# esp32_moisture.net
KiCad netlist of a schematic drawn in EAGLE
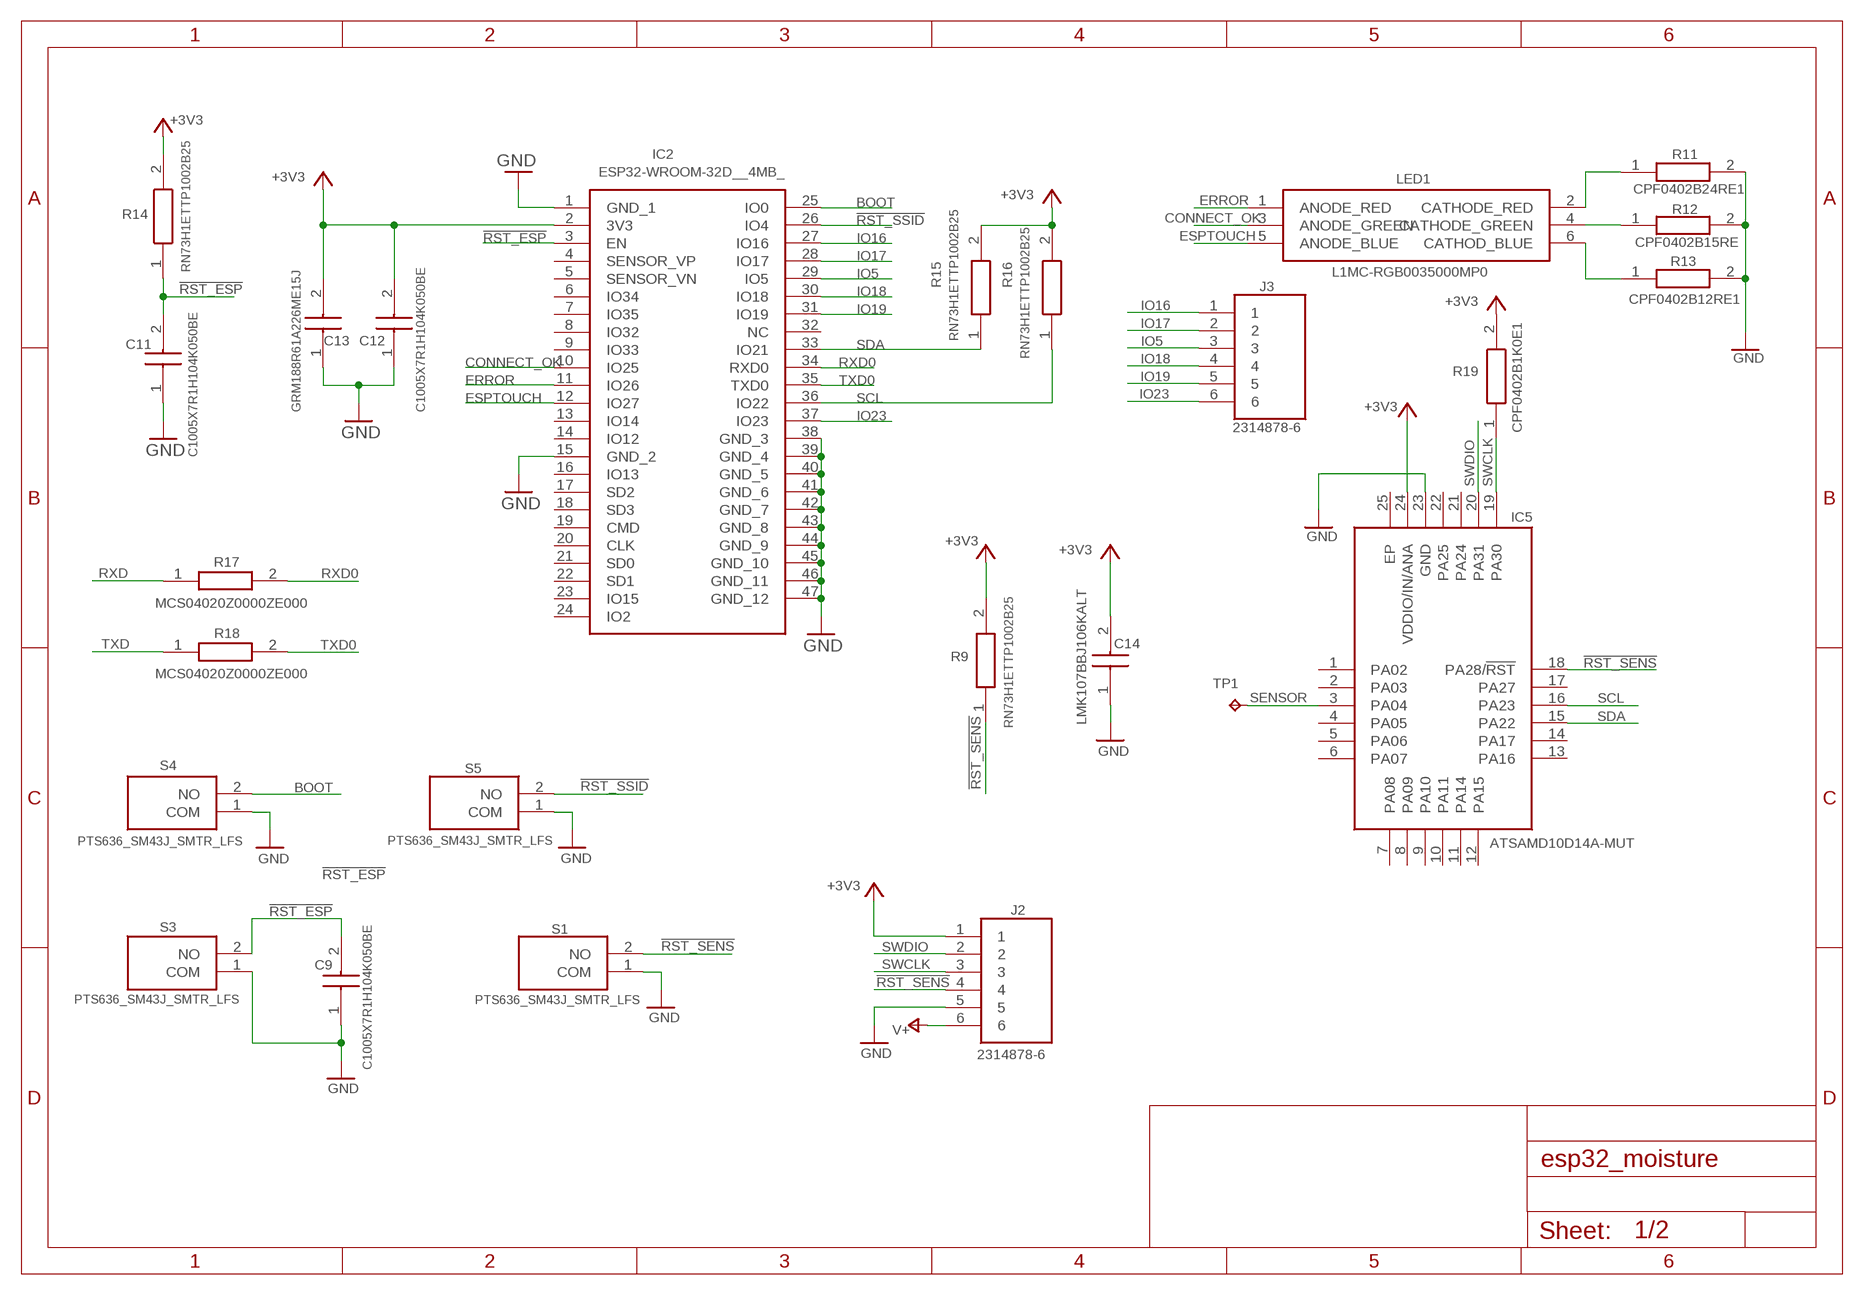
[diagram p0: schematic, sheet 1]
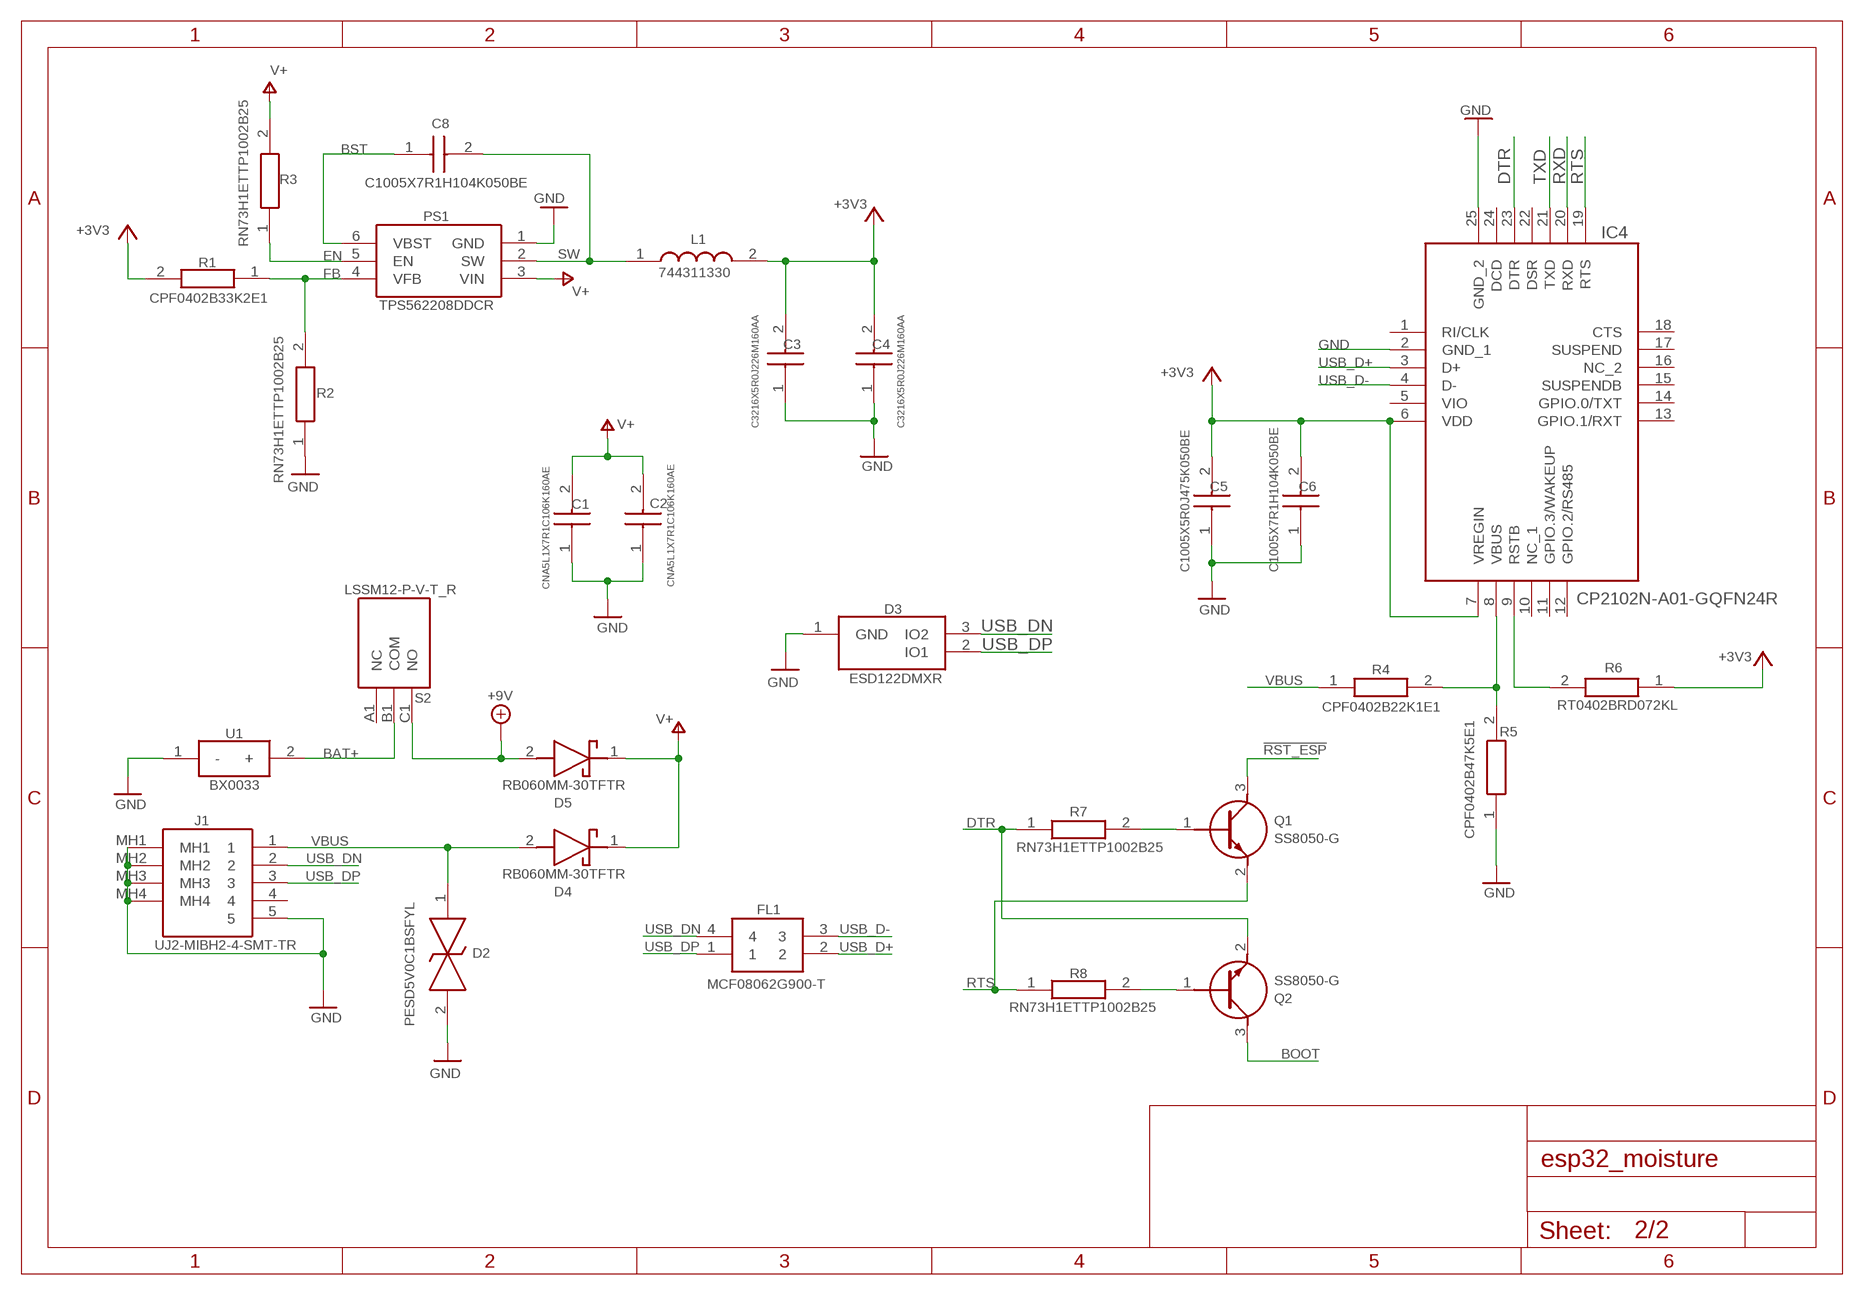
[diagram p1: schematic, sheet 2]

(export (version "E")
  (design (tool "Eeschema 10.0.6"))
  (components
    (comp (ref "C9")
      (value "C1005X7R1H104K050BE")
      (footprint "eagle-import:CAPC1005X55N")
      (fields (field (name "MOUSER2_PART_NUMBER") "810-C1005X7R1H104KBE"))
      (libsource (lib "eagle-import") (part "C1005X7R1H104K050BE"))
    )
    (comp (ref "C11")
      (value "C1005X7R1H104K050BE")
      (footprint "eagle-import:CAPC1005X55N")
      (fields (field (name "MOUSER2_PART_NUMBER") "810-C1005X7R1H104KBE"))
      (libsource (lib "eagle-import") (part "C1005X7R1H104K050BE"))
    )
    (comp (ref "C12")
      (value "C1005X7R1H104K050BE")
      (footprint "eagle-import:CAPC1005X55N")
      (fields (field (name "MOUSER2_PART_NUMBER") "810-C1005X7R1H104KBE"))
      (libsource (lib "eagle-import") (part "C1005X7R1H104K050BE"))
    )
    (comp (ref "C13")
      (value "GRM188R61A226ME15J")
      (footprint "eagle-import:CAPC1608X90N")
      (fields (field (name "MOUSER2_PART_NUMBER") "81-GRM188R61A226ME5J"))
      (libsource (lib "eagle-import") (part "GRM188R61A226ME15J"))
    )
    (comp (ref "C14")
      (value "LMK107BBJ106KALT")
      (footprint "eagle-import:CAPC1608X100N")
      (fields (field (name "MOUSER2_PART_NUMBER") "963-LMK107BBJ106KALT"))
      (libsource (lib "eagle-import") (part "LMK107BBJ106KALT"))
    )
    (comp (ref "IC2")
      (value "ESP32-WROOM-32D__4MB_")
      (footprint "eagle-import:ESP32WROOM32D4MB")
      (fields
        (field (name "MANUFACTURER_PART_NUMBER") "ESP32-WROOM-32D (4MB)")
        (field (name "MOUSER_PART_NUMBER") "356-ESP32WROOM-32D")
      )
      (libsource (lib "eagle-import") (part "ESP32-WROOM-32D__4MB_"))
    )
    (comp (ref "IC5")
      (value "ATSAMD10D14A-MUT")
      (footprint "eagle-import:QFN50P400X400X90-25N")
      (fields (field (name "MOUSER_PART_NUMBER") "556-ATSAMD10D14A-MUT"))
      (libsource (lib "eagle-import") (part "ATSAMD10D14A-MUT"))
    )
    (comp (ref "J2")
      (value "2314878-6")
      (footprint "eagle-import:RHDR6W40P0X200_1X6_1200X210X45")
      (libsource (lib "eagle-import") (part "2314878-6"))
    )
    (comp (ref "J3")
      (value "2314878-6")
      (footprint "eagle-import:RHDR6W40P0X200_1X6_1200X210X45")
      (libsource (lib "eagle-import") (part "2314878-6"))
    )
    (comp (ref "LED1")
      (value "L1MC-RGB0035000MP0")
      (footprint "eagle-import:L1MCRGB0035000MP0")
      (libsource (lib "eagle-import") (part "L1MC-RGB0035000MP0"))
    )
    (comp (ref "R9")
      (value "RN73H1ETTP1002B25")
      (footprint "eagle-import:RESC1005X40N")
      (fields (field (name "MOUSER2_PART_NUMBER") "660-RN73H1ETP1002B25"))
      (libsource (lib "eagle-import") (part "RN73H1ETTP1002B25"))
    )
    (comp (ref "R11")
      (value "CPF0402B24RE1")
      (footprint "eagle-import:RESC1005X35N")
      (libsource (lib "eagle-import") (part "CPF0402B24RE1"))
    )
    (comp (ref "R12")
      (value "CPF0402B15RE")
      (footprint "eagle-import:RESC1005X35N")
      (libsource (lib "eagle-import") (part "CPF0402B15RE"))
    )
    (comp (ref "R13")
      (value "CPF0402B12RE1")
      (footprint "eagle-import:RESC1005X35N")
      (libsource (lib "eagle-import") (part "CPF0402B12RE1"))
    )
    (comp (ref "R14")
      (value "RN73H1ETTP1002B25")
      (footprint "eagle-import:RESC1005X40N")
      (fields (field (name "MOUSER2_PART_NUMBER") "660-RN73H1ETP1002B25"))
      (libsource (lib "eagle-import") (part "RN73H1ETTP1002B25"))
    )
    (comp (ref "R15")
      (value "RN73H1ETTP1002B25")
      (footprint "eagle-import:RESC1005X40N")
      (fields (field (name "MOUSER2_PART_NUMBER") "660-RN73H1ETP1002B25"))
      (libsource (lib "eagle-import") (part "RN73H1ETTP1002B25"))
    )
    (comp (ref "R16")
      (value "RN73H1ETTP1002B25")
      (footprint "eagle-import:RESC1005X40N")
      (fields (field (name "MOUSER2_PART_NUMBER") "660-RN73H1ETP1002B25"))
      (libsource (lib "eagle-import") (part "RN73H1ETTP1002B25"))
    )
    (comp (ref "R17")
      (value "MCS04020Z0000ZE000")
      (footprint "eagle-import:RESC1005X37N")
      (libsource (lib "eagle-import") (part "MCS04020Z0000ZE000"))
    )
    (comp (ref "R18")
      (value "MCS04020Z0000ZE000")
      (footprint "eagle-import:RESC1005X37N")
      (libsource (lib "eagle-import") (part "MCS04020Z0000ZE000"))
    )
    (comp (ref "R19")
      (value "CPF0402B1K0E1")
      (footprint "eagle-import:RESC1005X35N")
      (fields (field (name "MOUSER2_PART_NUMBER") "279-CPF0402B1K0E1"))
      (libsource (lib "eagle-import") (part "CPF0402B1K0E1"))
    )
    (comp (ref "S1")
      (value "PTS636_SM43J_SMTR_LFS")
      (footprint "eagle-import:PTS636SM43JSMTRLFS")
      (fields (field (name "MANUFACTURER_PART_NUMBER") "PTS636 SM43J SMTR LFS"))
      (libsource (lib "eagle-import") (part "PTS636_SM43J_SMTR_LFS"))
    )
    (comp (ref "S3")
      (value "PTS636_SM43J_SMTR_LFS")
      (footprint "eagle-import:PTS636SM43JSMTRLFS")
      (fields (field (name "MANUFACTURER_PART_NUMBER") "PTS636 SM43J SMTR LFS"))
      (libsource (lib "eagle-import") (part "PTS636_SM43J_SMTR_LFS"))
    )
    (comp (ref "S4")
      (value "PTS636_SM43J_SMTR_LFS")
      (footprint "eagle-import:PTS636SM43JSMTRLFS")
      (fields (field (name "MANUFACTURER_PART_NUMBER") "PTS636 SM43J SMTR LFS"))
      (libsource (lib "eagle-import") (part "PTS636_SM43J_SMTR_LFS"))
    )
    (comp (ref "S5")
      (value "PTS636_SM43J_SMTR_LFS")
      (footprint "eagle-import:PTS636SM43JSMTRLFS")
      (fields (field (name "MANUFACTURER_PART_NUMBER") "PTS636 SM43J SMTR LFS"))
      (libsource (lib "eagle-import") (part "PTS636_SM43J_SMTR_LFS"))
    )
    (comp (ref "TP1")
      (value "TPTP15R")
      (footprint "eagle-import:TP15R")
      (libsource (lib "eagle-import") (part "TPTP15R"))
    )
    (comp (ref "C1")
      (value "CNA5L1X7R1C106K160AE")
      (footprint "eagle-import:CAPC3216X180N")
      (fields (field (name "MOUSER2_PART_NUMBER") "810-CNA5L1X7R1C106K1"))
      (libsource (lib "eagle-import") (part "CNA5L1X7R1C106K160AE"))
    )
    (comp (ref "C2")
      (value "CNA5L1X7R1C106K160AE")
      (footprint "eagle-import:CAPC3216X180N")
      (fields (field (name "MOUSER2_PART_NUMBER") "810-CNA5L1X7R1C106K1"))
      (libsource (lib "eagle-import") (part "CNA5L1X7R1C106K160AE"))
    )
    (comp (ref "C3")
      (value "C3216X5R0J226M160AA")
      (footprint "eagle-import:CAPC3216X180N")
      (libsource (lib "eagle-import") (part "C3216X5R0J226M160AA"))
    )
    (comp (ref "C4")
      (value "C3216X5R0J226M160AA")
      (footprint "eagle-import:CAPC3216X180N")
      (libsource (lib "eagle-import") (part "C3216X5R0J226M160AA"))
    )
    (comp (ref "C5")
      (value "C1005X5R0J475K050BE")
      (footprint "eagle-import:CAPC1005X55N")
      (libsource (lib "eagle-import") (part "C1005X5R0J475K050BE"))
    )
    (comp (ref "C6")
      (value "C1005X7R1H104K050BE")
      (footprint "eagle-import:CAPC1005X55N")
      (fields (field (name "MOUSER2_PART_NUMBER") "810-C1005X7R1H104KBE"))
      (libsource (lib "eagle-import") (part "C1005X7R1H104K050BE"))
    )
    (comp (ref "C8")
      (value "C1005X7R1H104K050BE")
      (footprint "eagle-import:CAPC1005X55N")
      (fields (field (name "MOUSER2_PART_NUMBER") "810-C1005X7R1H104KBE"))
      (libsource (lib "eagle-import") (part "C1005X7R1H104K050BE"))
    )
    (comp (ref "D2")
      (value "PESD5V0C1BSFYL")
      (footprint "eagle-import:PESD5V0S1USF315")
      (fields (field (name "MOUSER2_PART_NUMBER") "771-PESD5V0C1BSFYL"))
      (libsource (lib "eagle-import") (part "PESD5V0C1BSFYL"))
    )
    (comp (ref "D3")
      (value "ESD122DMXR")
      (footprint "eagle-import:DMX0003A")
      (libsource (lib "eagle-import") (part "ESD122DMXR"))
    )
    (comp (ref "D4")
      (value "RB060MM-30TFTR")
      (footprint "eagle-import:SODFL3516X90N")
      (fields (field (name "MOUSER2_PART_NUMBER") "755-RB060MM-30TFTR"))
      (libsource (lib "eagle-import") (part "RB060MM-30TFTR"))
    )
    (comp (ref "D5")
      (value "RB060MM-30TFTR")
      (footprint "eagle-import:SODFL3516X90N")
      (fields (field (name "MOUSER2_PART_NUMBER") "755-RB060MM-30TFTR"))
      (libsource (lib "eagle-import") (part "RB060MM-30TFTR"))
    )
    (comp (ref "FL1")
      (value "MCF08062G900-T")
      (footprint "eagle-import:MCF08062G900T")
      (fields (field (name "MOUSER_PART_NUMBER") "963-MCF08062G900-T"))
      (libsource (lib "eagle-import") (part "MCF08062G900-T"))
    )
    (comp (ref "IC4")
      (value "CP2102N-A01-GQFN24R")
      (footprint "eagle-import:QFN50P400X400X80-25N")
      (fields (field (name "MOUSER2_PART_NUMBER") "634-CP02NA01GQFN24R"))
      (libsource (lib "eagle-import") (part "CP2102N-A01-GQFN24R"))
    )
    (comp (ref "J1")
      (value "UJ2-MIBH2-4-SMT-TR")
      (footprint "eagle-import:UJ2MIBH24SMTTR")
      (fields (field (name "MOUSER2_PART_NUMBER") "490-UJ2-MIBH2-4-SMT"))
      (libsource (lib "eagle-import") (part "UJ2-MIBH2-4-SMT-TR"))
    )
    (comp (ref "L1")
      (value "744311330")
      (footprint "eagle-import:WE-HCI_7030_7040_705023")
      (libsource (lib "eagle-import") (part "744311330"))
    )
    (comp (ref "PS1")
      (value "TPS562208DDCR")
      (footprint "eagle-import:SOT95P280X110-6N")
      (fields (field (name "MOUSER_PART_NUMBER") "595-TPS562208DDCR"))
      (libsource (lib "eagle-import") (part "TPS562208DDCR"))
    )
    (comp (ref "Q1")
      (value "SS8050-G")
      (footprint "eagle-import:SOT95P240X115-3N")
      (fields (field (name "MOUSER2_PART_NUMBER") "750-SS8050-G"))
      (libsource (lib "eagle-import") (part "SS8050-G"))
    )
    (comp (ref "Q2")
      (value "SS8050-G")
      (footprint "eagle-import:SOT95P240X115-3N")
      (fields (field (name "MOUSER2_PART_NUMBER") "750-SS8050-G"))
      (libsource (lib "eagle-import") (part "SS8050-G"))
    )
    (comp (ref "R1")
      (value "CPF0402B33K2E1")
      (footprint "eagle-import:RESC1005X35N")
      (libsource (lib "eagle-import") (part "CPF0402B33K2E1"))
    )
    (comp (ref "R2")
      (value "RN73H1ETTP1002B25")
      (footprint "eagle-import:RESC1005X40N")
      (fields (field (name "MOUSER2_PART_NUMBER") "660-RN73H1ETP1002B25"))
      (libsource (lib "eagle-import") (part "RN73H1ETTP1002B25"))
    )
    (comp (ref "R3")
      (value "RN73H1ETTP1002B25")
      (footprint "eagle-import:RESC1005X40N")
      (fields (field (name "MOUSER2_PART_NUMBER") "660-RN73H1ETP1002B25"))
      (libsource (lib "eagle-import") (part "RN73H1ETTP1002B25"))
    )
    (comp (ref "R4")
      (value "CPF0402B22K1E1")
      (footprint "eagle-import:RESC1005X35N")
      (libsource (lib "eagle-import") (part "CPF0402B22K1E1"))
    )
    (comp (ref "R5")
      (value "CPF0402B47K5E1")
      (footprint "eagle-import:RESC1005X35N")
      (libsource (lib "eagle-import") (part "CPF0402B47K5E1"))
    )
    (comp (ref "R6")
      (value "RT0402BRD072KL")
      (footprint "eagle-import:RESC1005X35N")
      (libsource (lib "eagle-import") (part "RT0402BRD072KL"))
    )
    (comp (ref "R7")
      (value "RN73H1ETTP1002B25")
      (footprint "eagle-import:RESC1005X40N")
      (fields (field (name "MOUSER2_PART_NUMBER") "660-RN73H1ETP1002B25"))
      (libsource (lib "eagle-import") (part "RN73H1ETTP1002B25"))
    )
    (comp (ref "R8")
      (value "RN73H1ETTP1002B25")
      (footprint "eagle-import:RESC1005X40N")
      (fields (field (name "MOUSER2_PART_NUMBER") "660-RN73H1ETP1002B25"))
      (libsource (lib "eagle-import") (part "RN73H1ETTP1002B25"))
    )
    (comp (ref "S2")
      (value "LSSM12-P-V-T_R")
      (footprint "eagle-import:LSSM12PVTR")
      (fields
        (field (name "MANUFACTURER_PART_NUMBER") "LSSM12-P-V-T/R")
        (field (name "MOUSER_PART_NUMBER") "113-LSSM12PVT/R")
      )
      (libsource (lib "eagle-import") (part "LSSM12-P-V-T_R"))
    )
    (comp (ref "U1")
      (value "BX0033")
      (footprint "eagle-import:BX0033")
      (fields (field (name "MOUSER_PART_NUMBER") "122-BX0033"))
      (libsource (lib "eagle-import") (part "BX0033"))
    )
  )
  (nets
    (net (code "1") (name "+3V3") (class "Default")
      (node (ref "C12") (pin "2") (pinfunction "2_2") (pintype "bidirectional"))
      (node (ref "C13") (pin "2") (pinfunction "2_2") (pintype "bidirectional"))
      (node (ref "C14") (pin "2") (pinfunction "2_2") (pintype "bidirectional"))
      (node (ref "C3") (pin "2") (pinfunction "2_2") (pintype "bidirectional"))
      (node (ref "C4") (pin "2") (pinfunction "2_2") (pintype "bidirectional"))
      (node (ref "C5") (pin "2") (pinfunction "2_2") (pintype "bidirectional"))
      (node (ref "C6") (pin "2") (pinfunction "2_2") (pintype "bidirectional"))
      (node (ref "IC2") (pin "2") (pinfunction "3V3_2") (pintype "bidirectional"))
      (node (ref "IC4") (pin "6") (pinfunction "VDD_6") (pintype "bidirectional"))
      (node (ref "IC4") (pin "7") (pinfunction "VREGIN_7") (pintype "bidirectional"))
      (node (ref "IC5") (pin "24") (pinfunction "VDDIO/IN/ANA_24") (pintype "bidirectional"))
      (node (ref "J2") (pin "1") (pinfunction "1_1") (pintype "bidirectional"))
      (node (ref "L1") (pin "2") (pinfunction "2_2") (pintype "bidirectional"))
      (node (ref "R1") (pin "2") (pinfunction "2_2") (pintype "bidirectional"))
      (node (ref "R14") (pin "2") (pinfunction "2_2") (pintype "bidirectional"))
      (node (ref "R15") (pin "2") (pinfunction "2_2") (pintype "bidirectional"))
      (node (ref "R16") (pin "2") (pinfunction "2_2") (pintype "bidirectional"))
      (node (ref "R19") (pin "2") (pinfunction "2_2") (pintype "bidirectional"))
      (node (ref "R6") (pin "1") (pinfunction "1_1") (pintype "bidirectional"))
      (node (ref "R9") (pin "2") (pinfunction "2_2") (pintype "bidirectional"))
    )
    (net (code "2") (name "+9V") (class "Default")
      (node (ref "D5") (pin "2") (pinfunction "A_2") (pintype "bidirectional"))
      (node (ref "S2") (pin "C1") (pinfunction "NO_C1") (pintype "bidirectional"))
    )
    (net (code "3") (name "BAT+") (class "Default")
      (node (ref "S2") (pin "B1") (pinfunction "COM_B1") (pintype "bidirectional"))
      (node (ref "U1") (pin "2") (pinfunction "+_2") (pintype "bidirectional"))
    )
    (net (code "4") (name "BOOT") (class "Default")
      (node (ref "IC2") (pin "25") (pinfunction "IO0_25") (pintype "bidirectional"))
      (node (ref "Q2") (pin "3") (pinfunction "C_3") (pintype "bidirectional"))
      (node (ref "S4") (pin "2") (pinfunction "NO_2") (pintype "bidirectional"))
    )
    (net (code "5") (name "BST") (class "Default")
      (node (ref "C8") (pin "1") (pinfunction "1_1") (pintype "bidirectional"))
      (node (ref "PS1") (pin "6") (pinfunction "VBST_6") (pintype "bidirectional"))
    )
    (net (code "6") (name "CONNECT_OK") (class "Default")
      (node (ref "IC2") (pin "10") (pinfunction "IO25_10") (pintype "bidirectional"))
      (node (ref "LED1") (pin "3") (pinfunction "ANODE_GREEN_3") (pintype "bidirectional"))
    )
    (net (code "7") (name "DTR") (class "Default")
      (node (ref "IC4") (pin "23") (pinfunction "DTR_23") (pintype "bidirectional"))
      (node (ref "Q2") (pin "2") (pinfunction "E_2") (pintype "bidirectional"))
      (node (ref "R7") (pin "1") (pinfunction "1_1") (pintype "bidirectional"))
    )
    (net (code "8") (name "EN") (class "Default")
      (node (ref "PS1") (pin "5") (pinfunction "EN_5") (pintype "bidirectional"))
      (node (ref "R3") (pin "1") (pinfunction "1_1") (pintype "bidirectional"))
    )
    (net (code "9") (name "ERROR") (class "Default")
      (node (ref "IC2") (pin "11") (pinfunction "IO26_11") (pintype "bidirectional"))
      (node (ref "LED1") (pin "1") (pinfunction "ANODE_RED_1") (pintype "bidirectional"))
    )
    (net (code "10") (name "ESPTOUCH") (class "Default")
      (node (ref "IC2") (pin "12") (pinfunction "IO27_12") (pintype "bidirectional"))
      (node (ref "LED1") (pin "5") (pinfunction "ANODE_BLUE_5") (pintype "bidirectional"))
    )
    (net (code "11") (name "FB") (class "Default")
      (node (ref "PS1") (pin "4") (pinfunction "VFB_4") (pintype "bidirectional"))
      (node (ref "R1") (pin "1") (pinfunction "1_1") (pintype "bidirectional"))
      (node (ref "R2") (pin "2") (pinfunction "2_2") (pintype "bidirectional"))
    )
    (net (code "12") (name "GND") (class "Default")
      (node (ref "C1") (pin "1") (pinfunction "1_1") (pintype "bidirectional"))
      (node (ref "C11") (pin "1") (pinfunction "1_1") (pintype "bidirectional"))
      (node (ref "C12") (pin "1") (pinfunction "1_1") (pintype "bidirectional"))
      (node (ref "C13") (pin "1") (pinfunction "1_1") (pintype "bidirectional"))
      (node (ref "C14") (pin "1") (pinfunction "1_1") (pintype "bidirectional"))
      (node (ref "C2") (pin "1") (pinfunction "1_1") (pintype "bidirectional"))
      (node (ref "C3") (pin "1") (pinfunction "1_1") (pintype "bidirectional"))
      (node (ref "C4") (pin "1") (pinfunction "1_1") (pintype "bidirectional"))
      (node (ref "C5") (pin "1") (pinfunction "1_1") (pintype "bidirectional"))
      (node (ref "C6") (pin "1") (pinfunction "1_1") (pintype "bidirectional"))
      (node (ref "C9") (pin "1") (pinfunction "1_1") (pintype "bidirectional"))
      (node (ref "D2") (pin "2") (pinfunction "2_2") (pintype "bidirectional"))
      (node (ref "D3") (pin "1") (pinfunction "GND_1") (pintype "bidirectional"))
      (node (ref "IC2") (pin "1") (pinfunction "GND_1_1") (pintype "bidirectional"))
      (node (ref "IC2") (pin "15") (pinfunction "GND_2_15") (pintype "bidirectional"))
      (node (ref "IC2") (pin "38") (pinfunction "GND_3_38") (pintype "bidirectional"))
      (node (ref "IC2") (pin "39") (pinfunction "GND_4_39") (pintype "bidirectional"))
      (node (ref "IC2") (pin "40") (pinfunction "GND_5_40") (pintype "bidirectional"))
      (node (ref "IC2") (pin "41") (pinfunction "GND_6_41") (pintype "bidirectional"))
      (node (ref "IC2") (pin "42") (pinfunction "GND_7_42") (pintype "bidirectional"))
      (node (ref "IC2") (pin "43") (pinfunction "GND_8_43") (pintype "bidirectional"))
      (node (ref "IC2") (pin "44") (pinfunction "GND_9_44") (pintype "bidirectional"))
      (node (ref "IC2") (pin "45") (pinfunction "GND_10_45") (pintype "bidirectional"))
      (node (ref "IC2") (pin "46") (pinfunction "GND_11_46") (pintype "bidirectional"))
      (node (ref "IC2") (pin "47") (pinfunction "GND_12_47") (pintype "bidirectional"))
      (node (ref "IC4") (pin "2") (pinfunction "GND_1_2") (pintype "bidirectional"))
      (node (ref "IC4") (pin "25") (pinfunction "GND_2_25") (pintype "bidirectional"))
      (node (ref "IC5") (pin "23") (pinfunction "GND_23") (pintype "bidirectional"))
      (node (ref "J1") (pin "5") (pinfunction "5_5") (pintype "bidirectional"))
      (node (ref "J1") (pin "MH1") (pinfunction "MH1_MH1") (pintype "bidirectional"))
      (node (ref "J1") (pin "MH2") (pinfunction "MH2_MH2") (pintype "bidirectional"))
      (node (ref "J1") (pin "MH3") (pinfunction "MH3_MH3") (pintype "bidirectional"))
      (node (ref "J1") (pin "MH4") (pinfunction "MH4_MH4") (pintype "bidirectional"))
      (node (ref "J2") (pin "5") (pinfunction "5_5") (pintype "bidirectional"))
      (node (ref "PS1") (pin "1") (pinfunction "GND_1") (pintype "bidirectional"))
      (node (ref "R11") (pin "2") (pinfunction "2_2") (pintype "bidirectional"))
      (node (ref "R12") (pin "2") (pinfunction "2_2") (pintype "bidirectional"))
      (node (ref "R13") (pin "2") (pinfunction "2_2") (pintype "bidirectional"))
      (node (ref "R2") (pin "1") (pinfunction "1_1") (pintype "bidirectional"))
      (node (ref "R5") (pin "1") (pinfunction "1_1") (pintype "bidirectional"))
      (node (ref "S1") (pin "1") (pinfunction "COM_1") (pintype "bidirectional"))
      (node (ref "S3") (pin "1") (pinfunction "COM_1") (pintype "bidirectional"))
      (node (ref "S4") (pin "1") (pinfunction "COM_1") (pintype "bidirectional"))
      (node (ref "S5") (pin "1") (pinfunction "COM_1") (pintype "bidirectional"))
      (node (ref "U1") (pin "1") (pinfunction "-_1") (pintype "bidirectional"))
    )
    (net (code "13") (name "IO5") (class "Default")
      (node (ref "IC2") (pin "29") (pinfunction "IO5_29") (pintype "bidirectional"))
      (node (ref "J3") (pin "3") (pinfunction "3_3") (pintype "bidirectional"))
    )
    (net (code "14") (name "IO16") (class "Default")
      (node (ref "IC2") (pin "27") (pinfunction "IO16_27") (pintype "bidirectional"))
      (node (ref "J3") (pin "1") (pinfunction "1_1") (pintype "bidirectional"))
    )
    (net (code "15") (name "IO17") (class "Default")
      (node (ref "IC2") (pin "28") (pinfunction "IO17_28") (pintype "bidirectional"))
      (node (ref "J3") (pin "2") (pinfunction "2_2") (pintype "bidirectional"))
    )
    (net (code "16") (name "IO18") (class "Default")
      (node (ref "IC2") (pin "30") (pinfunction "IO18_30") (pintype "bidirectional"))
      (node (ref "J3") (pin "4") (pinfunction "4_4") (pintype "bidirectional"))
    )
    (net (code "17") (name "IO19") (class "Default")
      (node (ref "IC2") (pin "31") (pinfunction "IO19_31") (pintype "bidirectional"))
      (node (ref "J3") (pin "5") (pinfunction "5_5") (pintype "bidirectional"))
    )
    (net (code "18") (name "IO23") (class "Default")
      (node (ref "IC2") (pin "37") (pinfunction "IO23_37") (pintype "bidirectional"))
      (node (ref "J3") (pin "6") (pinfunction "6_6") (pintype "bidirectional"))
    )
    (net (code "19") (name "Net-(IC4-RSTB)") (class "Default")
      (node (ref "IC4") (pin "9") (pinfunction "RSTB_9") (pintype "bidirectional"))
      (node (ref "R6") (pin "2") (pinfunction "2_2") (pintype "bidirectional"))
    )
    (net (code "20") (name "Net-(IC4-VBUS)") (class "Default")
      (node (ref "IC4") (pin "8") (pinfunction "VBUS_8") (pintype "bidirectional"))
      (node (ref "R4") (pin "2") (pinfunction "2_2") (pintype "bidirectional"))
      (node (ref "R5") (pin "2") (pinfunction "2_2") (pintype "bidirectional"))
    )
    (net (code "21") (name "Net-(LED1-CATHODE_GREEN)") (class "Default")
      (node (ref "LED1") (pin "4") (pinfunction "CATHODE_GREEN_4") (pintype "bidirectional"))
      (node (ref "R12") (pin "1") (pinfunction "1_1") (pintype "bidirectional"))
    )
    (net (code "22") (name "Net-(LED1-CATHODE_RED)") (class "Default")
      (node (ref "LED1") (pin "2") (pinfunction "CATHODE_RED_2") (pintype "bidirectional"))
      (node (ref "R11") (pin "1") (pinfunction "1_1") (pintype "bidirectional"))
    )
    (net (code "23") (name "Net-(LED1-CATHOD_BLUE)") (class "Default")
      (node (ref "LED1") (pin "6") (pinfunction "CATHOD_BLUE_6") (pintype "bidirectional"))
      (node (ref "R13") (pin "1") (pinfunction "1_1") (pintype "bidirectional"))
    )
    (net (code "24") (name "Net-(Q1-B)") (class "Default")
      (node (ref "Q1") (pin "1") (pinfunction "B_1") (pintype "bidirectional"))
      (node (ref "R7") (pin "2") (pinfunction "2_2") (pintype "bidirectional"))
    )
    (net (code "25") (name "Net-(Q2-B)") (class "Default")
      (node (ref "Q2") (pin "1") (pinfunction "B_1") (pintype "bidirectional"))
      (node (ref "R8") (pin "2") (pinfunction "2_2") (pintype "bidirectional"))
    )
    (net (code "26") (name "RTS") (class "Default")
      (node (ref "IC4") (pin "19") (pinfunction "RTS_19") (pintype "bidirectional"))
      (node (ref "Q1") (pin "2") (pinfunction "E_2") (pintype "bidirectional"))
      (node (ref "R8") (pin "1") (pinfunction "1_1") (pintype "bidirectional"))
    )
    (net (code "27") (name "RXD") (class "Default")
      (node (ref "IC4") (pin "20") (pinfunction "RXD_20") (pintype "bidirectional"))
      (node (ref "R17") (pin "1") (pinfunction "1_1") (pintype "bidirectional"))
    )
    (net (code "28") (name "RXD0") (class "Default")
      (node (ref "IC2") (pin "34") (pinfunction "RXD0_34") (pintype "bidirectional"))
      (node (ref "R17") (pin "2") (pinfunction "2_2") (pintype "bidirectional"))
    )
    (net (code "29") (name "SCL") (class "Default")
      (node (ref "IC2") (pin "36") (pinfunction "IO22_36") (pintype "bidirectional"))
      (node (ref "IC5") (pin "16") (pinfunction "PA23_16") (pintype "bidirectional"))
      (node (ref "R16") (pin "1") (pinfunction "1_1") (pintype "bidirectional"))
    )
    (net (code "30") (name "SDA") (class "Default")
      (node (ref "IC2") (pin "33") (pinfunction "IO21_33") (pintype "bidirectional"))
      (node (ref "IC5") (pin "15") (pinfunction "PA22_15") (pintype "bidirectional"))
      (node (ref "R15") (pin "1") (pinfunction "1_1") (pintype "bidirectional"))
    )
    (net (code "31") (name "SENSOR") (class "Default")
      (node (ref "IC5") (pin "3") (pinfunction "PA04_3") (pintype "bidirectional"))
      (node (ref "TP1") (pin "TP") (pinfunction "TP_TP") (pintype "input"))
    )
    (net (code "32") (name "SW") (class "Default")
      (node (ref "C8") (pin "2") (pinfunction "2_2") (pintype "bidirectional"))
      (node (ref "L1") (pin "1") (pinfunction "1_1") (pintype "bidirectional"))
      (node (ref "PS1") (pin "2") (pinfunction "SW_2") (pintype "bidirectional"))
    )
    (net (code "33") (name "SWCLK") (class "Default")
      (node (ref "IC5") (pin "19") (pinfunction "PA30_19") (pintype "bidirectional"))
      (node (ref "J2") (pin "3") (pinfunction "3_3") (pintype "bidirectional"))
      (node (ref "R19") (pin "1") (pinfunction "1_1") (pintype "bidirectional"))
    )
    (net (code "34") (name "SWDIO") (class "Default")
      (node (ref "IC5") (pin "20") (pinfunction "PA31_20") (pintype "bidirectional"))
      (node (ref "J2") (pin "2") (pinfunction "2_2") (pintype "bidirectional"))
    )
    (net (code "35") (name "TXD") (class "Default")
      (node (ref "IC4") (pin "21") (pinfunction "TXD_21") (pintype "bidirectional"))
      (node (ref "R18") (pin "1") (pinfunction "1_1") (pintype "bidirectional"))
    )
    (net (code "36") (name "TXD0") (class "Default")
      (node (ref "IC2") (pin "35") (pinfunction "TXD0_35") (pintype "bidirectional"))
      (node (ref "R18") (pin "2") (pinfunction "2_2") (pintype "bidirectional"))
    )
    (net (code "37") (name "USB_D+") (class "Default")
      (node (ref "FL1") (pin "2") (pinfunction "2_2") (pintype "bidirectional"))
      (node (ref "IC4") (pin "3") (pinfunction "D+_3") (pintype "bidirectional"))
    )
    (net (code "38") (name "USB_D-") (class "Default")
      (node (ref "FL1") (pin "3") (pinfunction "3_3") (pintype "bidirectional"))
      (node (ref "IC4") (pin "4") (pinfunction "D-_4") (pintype "bidirectional"))
    )
    (net (code "39") (name "USB_DN") (class "Default")
      (node (ref "D3") (pin "3") (pinfunction "IO2_3") (pintype "bidirectional"))
      (node (ref "FL1") (pin "4") (pinfunction "4_4") (pintype "bidirectional"))
      (node (ref "J1") (pin "2") (pinfunction "2_2") (pintype "bidirectional"))
    )
    (net (code "40") (name "USB_DP") (class "Default")
      (node (ref "D3") (pin "2") (pinfunction "IO1_2") (pintype "bidirectional"))
      (node (ref "FL1") (pin "1") (pinfunction "1_1") (pintype "bidirectional"))
      (node (ref "J1") (pin "3") (pinfunction "3_3") (pintype "bidirectional"))
    )
    (net (code "41") (name "V+") (class "Default")
      (node (ref "C1") (pin "2") (pinfunction "2_2") (pintype "bidirectional"))
      (node (ref "C2") (pin "2") (pinfunction "2_2") (pintype "bidirectional"))
      (node (ref "D4") (pin "1") (pinfunction "K_1") (pintype "bidirectional"))
      (node (ref "D5") (pin "1") (pinfunction "K_1") (pintype "bidirectional"))
      (node (ref "J2") (pin "6") (pinfunction "6_6") (pintype "bidirectional"))
      (node (ref "PS1") (pin "3") (pinfunction "VIN_3") (pintype "bidirectional"))
      (node (ref "R3") (pin "2") (pinfunction "2_2") (pintype "bidirectional"))
    )
    (net (code "42") (name "VBUS") (class "Default")
      (node (ref "D2") (pin "1") (pinfunction "1_1") (pintype "bidirectional"))
      (node (ref "D4") (pin "2") (pinfunction "A_2") (pintype "bidirectional"))
      (node (ref "J1") (pin "1") (pinfunction "1_1") (pintype "bidirectional"))
      (node (ref "R4") (pin "1") (pinfunction "1_1") (pintype "bidirectional"))
    )
    (net (code "43") (name "unconnected-(IC2-CLK-Pad20)") (class "Default")
      (node (ref "IC2") (pin "20") (pinfunction "CLK_20") (pintype "bidirectional"))
    )
    (net (code "44") (name "unconnected-(IC2-CMD-Pad19)") (class "Default")
      (node (ref "IC2") (pin "19") (pinfunction "CMD_19") (pintype "bidirectional"))
    )
    (net (code "45") (name "unconnected-(IC2-IO2-Pad24)") (class "Default")
      (node (ref "IC2") (pin "24") (pinfunction "IO2_24") (pintype "bidirectional"))
    )
    (net (code "46") (name "unconnected-(IC2-IO12-Pad14)") (class "Default")
      (node (ref "IC2") (pin "14") (pinfunction "IO12_14") (pintype "bidirectional"))
    )
    (net (code "47") (name "unconnected-(IC2-IO13-Pad16)") (class "Default")
      (node (ref "IC2") (pin "16") (pinfunction "IO13_16") (pintype "bidirectional"))
    )
    (net (code "48") (name "unconnected-(IC2-IO14-Pad13)") (class "Default")
      (node (ref "IC2") (pin "13") (pinfunction "IO14_13") (pintype "bidirectional"))
    )
    (net (code "49") (name "unconnected-(IC2-IO15-Pad23)") (class "Default")
      (node (ref "IC2") (pin "23") (pinfunction "IO15_23") (pintype "bidirectional"))
    )
    (net (code "50") (name "unconnected-(IC2-IO32-Pad8)") (class "Default")
      (node (ref "IC2") (pin "8") (pinfunction "IO32_8") (pintype "bidirectional"))
    )
    (net (code "51") (name "unconnected-(IC2-IO33-Pad9)") (class "Default")
      (node (ref "IC2") (pin "9") (pinfunction "IO33_9") (pintype "bidirectional"))
    )
    (net (code "52") (name "unconnected-(IC2-IO34-Pad6)") (class "Default")
      (node (ref "IC2") (pin "6") (pinfunction "IO34_6") (pintype "bidirectional"))
    )
    (net (code "53") (name "unconnected-(IC2-IO35-Pad7)") (class "Default")
      (node (ref "IC2") (pin "7") (pinfunction "IO35_7") (pintype "bidirectional"))
    )
    (net (code "54") (name "unconnected-(IC2-NC-Pad32)") (class "Default")
      (node (ref "IC2") (pin "32") (pinfunction "NC_32") (pintype "no_connect"))
    )
    (net (code "55") (name "unconnected-(IC2-SD0-Pad21)") (class "Default")
      (node (ref "IC2") (pin "21") (pinfunction "SD0_21") (pintype "bidirectional"))
    )
    (net (code "56") (name "unconnected-(IC2-SD1-Pad22)") (class "Default")
      (node (ref "IC2") (pin "22") (pinfunction "SD1_22") (pintype "bidirectional"))
    )
    (net (code "57") (name "unconnected-(IC2-SD2-Pad17)") (class "Default")
      (node (ref "IC2") (pin "17") (pinfunction "SD2_17") (pintype "bidirectional"))
    )
    (net (code "58") (name "unconnected-(IC2-SD3-Pad18)") (class "Default")
      (node (ref "IC2") (pin "18") (pinfunction "SD3_18") (pintype "bidirectional"))
    )
    (net (code "59") (name "unconnected-(IC2-SENSOR_VN-Pad5)") (class "Default")
      (node (ref "IC2") (pin "5") (pinfunction "SENSOR_VN_5") (pintype "bidirectional"))
    )
    (net (code "60") (name "unconnected-(IC2-SENSOR_VP-Pad4)") (class "Default")
      (node (ref "IC2") (pin "4") (pinfunction "SENSOR_VP_4") (pintype "bidirectional"))
    )
    (net (code "61") (name "unconnected-(IC4-CTS-Pad18)") (class "Default")
      (node (ref "IC4") (pin "18") (pinfunction "CTS_18") (pintype "bidirectional"))
    )
    (net (code "62") (name "unconnected-(IC4-DCD-Pad24)") (class "Default")
      (node (ref "IC4") (pin "24") (pinfunction "DCD_24") (pintype "bidirectional"))
    )
    (net (code "63") (name "unconnected-(IC4-DSR-Pad22)") (class "Default")
      (node (ref "IC4") (pin "22") (pinfunction "DSR_22") (pintype "bidirectional"))
    )
    (net (code "64") (name "unconnected-(IC4-GPIO.0{slash}TXT-Pad14)") (class "Default")
      (node (ref "IC4") (pin "14") (pinfunction "GPIO.0/TXT_14") (pintype "bidirectional"))
    )
    (net (code "65") (name "unconnected-(IC4-GPIO.1{slash}RXT-Pad13)") (class "Default")
      (node (ref "IC4") (pin "13") (pinfunction "GPIO.1/RXT_13") (pintype "bidirectional"))
    )
    (net (code "66") (name "unconnected-(IC4-GPIO.2{slash}RS485-Pad12)") (class "Default")
      (node (ref "IC4") (pin "12") (pinfunction "GPIO.2/RS485_12") (pintype "bidirectional"))
    )
    (net (code "67") (name "unconnected-(IC4-GPIO.3{slash}WAKEUP-Pad11)") (class "Default")
      (node (ref "IC4") (pin "11") (pinfunction "GPIO.3/WAKEUP_11") (pintype "bidirectional"))
    )
    (net (code "68") (name "unconnected-(IC4-NC_1-Pad10)") (class "Default")
      (node (ref "IC4") (pin "10") (pinfunction "NC_1_10") (pintype "bidirectional"))
    )
    (net (code "69") (name "unconnected-(IC4-NC_2-Pad16)") (class "Default")
      (node (ref "IC4") (pin "16") (pinfunction "NC_2_16") (pintype "bidirectional"))
    )
    (net (code "70") (name "unconnected-(IC4-RI{slash}CLK-Pad1)") (class "Default")
      (node (ref "IC4") (pin "1") (pinfunction "RI/CLK_1") (pintype "bidirectional"))
    )
    (net (code "71") (name "unconnected-(IC4-SUSPEND-Pad17)") (class "Default")
      (node (ref "IC4") (pin "17") (pinfunction "SUSPEND_17") (pintype "bidirectional"))
    )
    (net (code "72") (name "unconnected-(IC4-SUSPENDB-Pad15)") (class "Default")
      (node (ref "IC4") (pin "15") (pinfunction "SUSPENDB_15") (pintype "bidirectional"))
    )
    (net (code "73") (name "unconnected-(IC4-VIO-Pad5)") (class "Default")
      (node (ref "IC4") (pin "5") (pinfunction "VIO_5") (pintype "bidirectional"))
    )
    (net (code "74") (name "unconnected-(IC5-EP-Pad25)") (class "Default")
      (node (ref "IC5") (pin "25") (pinfunction "EP_25") (pintype "bidirectional"))
    )
    (net (code "75") (name "unconnected-(IC5-PA02-Pad1)") (class "Default")
      (node (ref "IC5") (pin "1") (pinfunction "PA02_1") (pintype "bidirectional"))
    )
    (net (code "76") (name "unconnected-(IC5-PA03-Pad2)") (class "Default")
      (node (ref "IC5") (pin "2") (pinfunction "PA03_2") (pintype "bidirectional"))
    )
    (net (code "77") (name "unconnected-(IC5-PA05-Pad4)") (class "Default")
      (node (ref "IC5") (pin "4") (pinfunction "PA05_4") (pintype "bidirectional"))
    )
    (net (code "78") (name "unconnected-(IC5-PA06-Pad5)") (class "Default")
      (node (ref "IC5") (pin "5") (pinfunction "PA06_5") (pintype "bidirectional"))
    )
    (net (code "79") (name "unconnected-(IC5-PA07-Pad6)") (class "Default")
      (node (ref "IC5") (pin "6") (pinfunction "PA07_6") (pintype "bidirectional"))
    )
    (net (code "80") (name "unconnected-(IC5-PA08-Pad7)") (class "Default")
      (node (ref "IC5") (pin "7") (pinfunction "PA08_7") (pintype "bidirectional"))
    )
    (net (code "81") (name "unconnected-(IC5-PA09-Pad8)") (class "Default")
      (node (ref "IC5") (pin "8") (pinfunction "PA09_8") (pintype "bidirectional"))
    )
    (net (code "82") (name "unconnected-(IC5-PA10-Pad9)") (class "Default")
      (node (ref "IC5") (pin "9") (pinfunction "PA10_9") (pintype "bidirectional"))
    )
    (net (code "83") (name "unconnected-(IC5-PA11-Pad10)") (class "Default")
      (node (ref "IC5") (pin "10") (pinfunction "PA11_10") (pintype "bidirectional"))
    )
    (net (code "84") (name "unconnected-(IC5-PA14-Pad11)") (class "Default")
      (node (ref "IC5") (pin "11") (pinfunction "PA14_11") (pintype "bidirectional"))
    )
    (net (code "85") (name "unconnected-(IC5-PA15-Pad12)") (class "Default")
      (node (ref "IC5") (pin "12") (pinfunction "PA15_12") (pintype "bidirectional"))
    )
    (net (code "86") (name "unconnected-(IC5-PA16-Pad13)") (class "Default")
      (node (ref "IC5") (pin "13") (pinfunction "PA16_13") (pintype "bidirectional"))
    )
    (net (code "87") (name "unconnected-(IC5-PA17-Pad14)") (class "Default")
      (node (ref "IC5") (pin "14") (pinfunction "PA17_14") (pintype "bidirectional"))
    )
    (net (code "88") (name "unconnected-(IC5-PA24-Pad21)") (class "Default")
      (node (ref "IC5") (pin "21") (pinfunction "PA24_21") (pintype "bidirectional"))
    )
    (net (code "89") (name "unconnected-(IC5-PA25-Pad22)") (class "Default")
      (node (ref "IC5") (pin "22") (pinfunction "PA25_22") (pintype "bidirectional"))
    )
    (net (code "90") (name "unconnected-(IC5-PA27-Pad17)") (class "Default")
      (node (ref "IC5") (pin "17") (pinfunction "PA27_17") (pintype "bidirectional"))
    )
    (net (code "91") (name "unconnected-(J1-Pad4)") (class "Default")
      (node (ref "J1") (pin "4") (pinfunction "4_4") (pintype "bidirectional"))
    )
    (net (code "92") (name "unconnected-(S2-NC-PadA1)") (class "Default")
      (node (ref "S2") (pin "A1") (pinfunction "NC_A1") (pintype "no_connect"))
    )
    (net (code "93") (name "~{RST_ESP}") (class "Default")
      (node (ref "C11") (pin "2") (pinfunction "2_2") (pintype "bidirectional"))
      (node (ref "C9") (pin "2") (pinfunction "2_2") (pintype "bidirectional"))
      (node (ref "IC2") (pin "3") (pinfunction "EN_3") (pintype "bidirectional"))
      (node (ref "Q1") (pin "3") (pinfunction "C_3") (pintype "bidirectional"))
      (node (ref "R14") (pin "1") (pinfunction "1_1") (pintype "bidirectional"))
      (node (ref "S3") (pin "2") (pinfunction "NO_2") (pintype "bidirectional"))
    )
    (net (code "94") (name "~{RST_SENS}") (class "Default")
      (node (ref "IC5") (pin "18") (pinfunction "PA28/~{RST}_18") (pintype "bidirectional"))
      (node (ref "J2") (pin "4") (pinfunction "4_4") (pintype "bidirectional"))
      (node (ref "R9") (pin "1") (pinfunction "1_1") (pintype "bidirectional"))
      (node (ref "S1") (pin "2") (pinfunction "NO_2") (pintype "bidirectional"))
    )
    (net (code "95") (name "~{RST_SSID}") (class "Default")
      (node (ref "IC2") (pin "26") (pinfunction "IO4_26") (pintype "bidirectional"))
      (node (ref "S5") (pin "2") (pinfunction "NO_2") (pintype "bidirectional"))
    )
  )
)
